# nandlogic.net
KiCad netlist of a schematic drawn in EAGLE
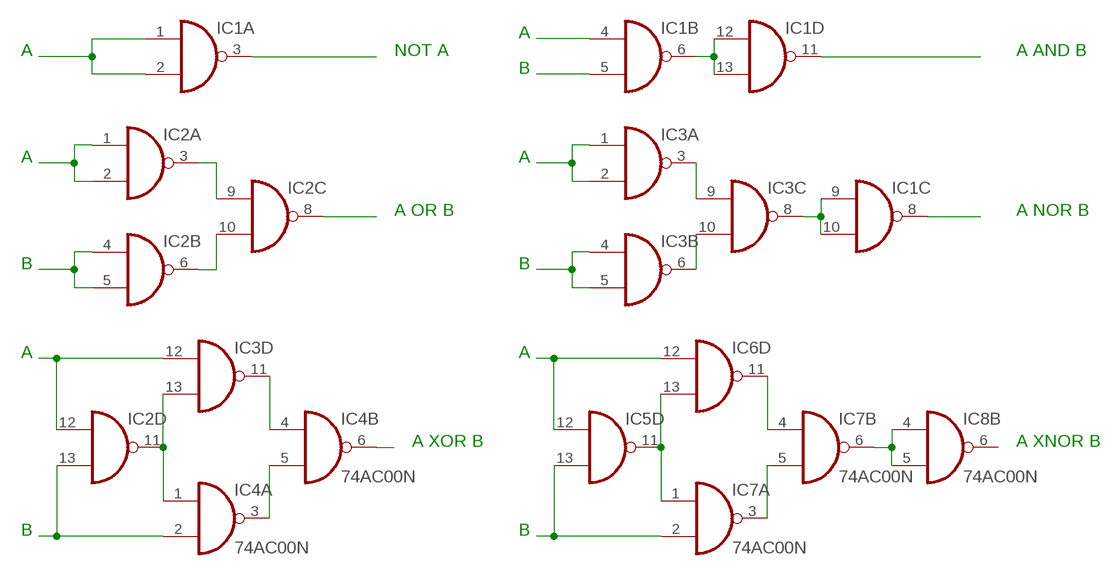
[diagram p0: schematic, sheet 1]

(export (version "E")
  (design (tool "Eeschema 10.0.6"))
  (components
    (comp (ref "IC1")
      (value "74AC00N")
      (footprint "eagle-import:DIL14")
      (libsource (lib "eagle-import") (part "7400NAC"))
    )
    (comp (ref "IC2")
      (value "74AC00N")
      (footprint "eagle-import:DIL14")
      (libsource (lib "eagle-import") (part "7400NAC"))
    )
    (comp (ref "IC3")
      (value "74AC00N")
      (footprint "eagle-import:DIL14")
      (libsource (lib "eagle-import") (part "7400NAC"))
    )
    (comp (ref "IC4")
      (value "74AC00N")
      (footprint "eagle-import:DIL14")
      (libsource (lib "eagle-import") (part "7400NAC"))
    )
    (comp (ref "IC5")
      (value "74AC00N")
      (footprint "eagle-import:DIL14")
      (libsource (lib "eagle-import") (part "7400NAC"))
    )
    (comp (ref "IC6")
      (value "74AC00N")
      (footprint "eagle-import:DIL14")
      (libsource (lib "eagle-import") (part "7400NAC"))
    )
    (comp (ref "IC7")
      (value "74AC00N")
      (footprint "eagle-import:DIL14")
      (libsource (lib "eagle-import") (part "7400NAC"))
    )
    (comp (ref "IC8")
      (value "74AC00N")
      (footprint "eagle-import:DIL14")
      (libsource (lib "eagle-import") (part "7400NAC"))
    )
  )
  (nets
    (net (code "1") (name "Net-(IC1A-I0)") (class "Default")
      (node (ref "IC1") (pin "1") (pinfunction "I0_1") (pintype "input"))
      (node (ref "IC1") (pin "2") (pinfunction "I1_2") (pintype "input"))
    )
    (net (code "2") (name "Net-(IC1B-O)") (class "Default")
      (node (ref "IC1") (pin "12") (pinfunction "I0_12") (pintype "input"))
      (node (ref "IC1") (pin "13") (pinfunction "I1_13") (pintype "input"))
      (node (ref "IC1") (pin "6") (pinfunction "O_6") (pintype "output"))
    )
    (net (code "3") (name "Net-(IC1C-I0)") (class "Default")
      (node (ref "IC1") (pin "10") (pinfunction "I1_10") (pintype "input"))
      (node (ref "IC1") (pin "9") (pinfunction "I0_9") (pintype "input"))
      (node (ref "IC3") (pin "8") (pinfunction "O_8") (pintype "output"))
    )
    (net (code "4") (name "Net-(IC2A-I0)") (class "Default")
      (node (ref "IC2") (pin "1") (pinfunction "I0_1") (pintype "input"))
      (node (ref "IC2") (pin "2") (pinfunction "I1_2") (pintype "input"))
    )
    (net (code "5") (name "Net-(IC2A-O)") (class "Default")
      (node (ref "IC2") (pin "3") (pinfunction "O_3") (pintype "output"))
      (node (ref "IC2") (pin "9") (pinfunction "I0_9") (pintype "input"))
    )
    (net (code "6") (name "Net-(IC2B-I0)") (class "Default")
      (node (ref "IC2") (pin "4") (pinfunction "I0_4") (pintype "input"))
      (node (ref "IC2") (pin "5") (pinfunction "I1_5") (pintype "input"))
    )
    (net (code "7") (name "Net-(IC2B-O)") (class "Default")
      (node (ref "IC2") (pin "10") (pinfunction "I1_10") (pintype "input"))
      (node (ref "IC2") (pin "6") (pinfunction "O_6") (pintype "output"))
    )
    (net (code "8") (name "Net-(IC2D-I0)") (class "Default")
      (node (ref "IC2") (pin "12") (pinfunction "I0_12") (pintype "input"))
      (node (ref "IC3") (pin "12") (pinfunction "I0_12") (pintype "input"))
    )
    (net (code "9") (name "Net-(IC2D-I1)") (class "Default")
      (node (ref "IC2") (pin "13") (pinfunction "I1_13") (pintype "input"))
      (node (ref "IC4") (pin "2") (pinfunction "I1_2") (pintype "input"))
    )
    (net (code "10") (name "Net-(IC2D-O)") (class "Default")
      (node (ref "IC2") (pin "11") (pinfunction "O_11") (pintype "output"))
      (node (ref "IC3") (pin "13") (pinfunction "I1_13") (pintype "input"))
      (node (ref "IC4") (pin "1") (pinfunction "I0_1") (pintype "input"))
    )
    (net (code "11") (name "Net-(IC3A-I0)") (class "Default")
      (node (ref "IC3") (pin "1") (pinfunction "I0_1") (pintype "input"))
      (node (ref "IC3") (pin "2") (pinfunction "I1_2") (pintype "input"))
    )
    (net (code "12") (name "Net-(IC3A-O)") (class "Default")
      (node (ref "IC3") (pin "3") (pinfunction "O_3") (pintype "output"))
      (node (ref "IC3") (pin "9") (pinfunction "I0_9") (pintype "input"))
    )
    (net (code "13") (name "Net-(IC3B-I0)") (class "Default")
      (node (ref "IC3") (pin "4") (pinfunction "I0_4") (pintype "input"))
      (node (ref "IC3") (pin "5") (pinfunction "I1_5") (pintype "input"))
    )
    (net (code "14") (name "Net-(IC3B-O)") (class "Default")
      (node (ref "IC3") (pin "10") (pinfunction "I1_10") (pintype "input"))
      (node (ref "IC3") (pin "6") (pinfunction "O_6") (pintype "output"))
    )
    (net (code "15") (name "Net-(IC3D-O)") (class "Default")
      (node (ref "IC3") (pin "11") (pinfunction "O_11") (pintype "output"))
      (node (ref "IC4") (pin "4") (pinfunction "I0_4") (pintype "input"))
    )
    (net (code "16") (name "Net-(IC4A-O)") (class "Default")
      (node (ref "IC4") (pin "3") (pinfunction "O_3") (pintype "output"))
      (node (ref "IC4") (pin "5") (pinfunction "I1_5") (pintype "input"))
    )
    (net (code "17") (name "Net-(IC5D-I0)") (class "Default")
      (node (ref "IC5") (pin "12") (pinfunction "I0_12") (pintype "input"))
      (node (ref "IC6") (pin "12") (pinfunction "I0_12") (pintype "input"))
    )
    (net (code "18") (name "Net-(IC5D-I1)") (class "Default")
      (node (ref "IC5") (pin "13") (pinfunction "I1_13") (pintype "input"))
      (node (ref "IC7") (pin "2") (pinfunction "I1_2") (pintype "input"))
    )
    (net (code "19") (name "Net-(IC5D-O)") (class "Default")
      (node (ref "IC5") (pin "11") (pinfunction "O_11") (pintype "output"))
      (node (ref "IC6") (pin "13") (pinfunction "I1_13") (pintype "input"))
      (node (ref "IC7") (pin "1") (pinfunction "I0_1") (pintype "input"))
    )
    (net (code "20") (name "Net-(IC6D-O)") (class "Default")
      (node (ref "IC6") (pin "11") (pinfunction "O_11") (pintype "output"))
      (node (ref "IC7") (pin "4") (pinfunction "I0_4") (pintype "input"))
    )
    (net (code "21") (name "Net-(IC7A-O)") (class "Default")
      (node (ref "IC7") (pin "3") (pinfunction "O_3") (pintype "output"))
      (node (ref "IC7") (pin "5") (pinfunction "I1_5") (pintype "input"))
    )
    (net (code "22") (name "Net-(IC7B-O)") (class "Default")
      (node (ref "IC7") (pin "6") (pinfunction "O_6") (pintype "output"))
      (node (ref "IC8") (pin "4") (pinfunction "I0_4") (pintype "input"))
      (node (ref "IC8") (pin "5") (pinfunction "I1_5") (pintype "input"))
    )
    (net (code "23") (name "unconnected-(IC1A-O-Pad3)") (class "Default")
      (node (ref "IC1") (pin "3") (pinfunction "O_3") (pintype "output"))
    )
    (net (code "24") (name "unconnected-(IC1B-I0-Pad4)") (class "Default")
      (node (ref "IC1") (pin "4") (pinfunction "I0_4") (pintype "input"))
    )
    (net (code "25") (name "unconnected-(IC1B-I1-Pad5)") (class "Default")
      (node (ref "IC1") (pin "5") (pinfunction "I1_5") (pintype "input"))
    )
    (net (code "26") (name "unconnected-(IC1C-O-Pad8)") (class "Default")
      (node (ref "IC1") (pin "8") (pinfunction "O_8") (pintype "output"))
    )
    (net (code "27") (name "unconnected-(IC1D-O-Pad11)") (class "Default")
      (node (ref "IC1") (pin "11") (pinfunction "O_11") (pintype "output"))
    )
    (net (code "28") (name "unconnected-(IC2C-O-Pad8)") (class "Default")
      (node (ref "IC2") (pin "8") (pinfunction "O_8") (pintype "output"))
    )
    (net (code "29") (name "unconnected-(IC4B-O-Pad6)") (class "Default")
      (node (ref "IC4") (pin "6") (pinfunction "O_6") (pintype "output"))
    )
    (net (code "30") (name "unconnected-(IC8B-O-Pad6)") (class "Default")
      (node (ref "IC8") (pin "6") (pinfunction "O_6") (pintype "output"))
    )
  )
)
